# PMOD_OV7670.net
KiCad netlist of a schematic drawn in Altium Designer
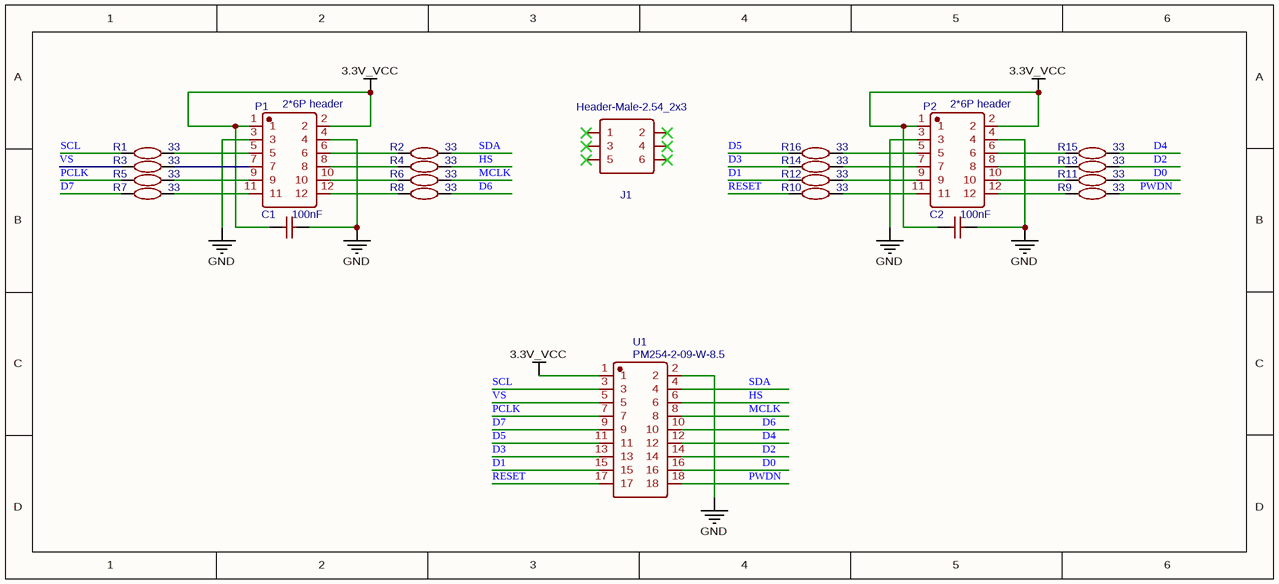
[diagram p0: PMOD_OV7670.schdoc]

(export (version "E")
  (design (tool "Eeschema 10.0.6"))
  (components
    (comp (ref "C1")
      (value "100nF")
      (footprint "C0603")
      (fields
        (field (name "BOM_MANUFACTURER PART") "CL10F104ZB8NNNC")
        (field (name "BOM_SUPPLIER PART") "C1688")
      )
      (libsource (lib "altium-import") (part "root_0_100nF_"))
    )
    (comp (ref "C2")
      (value "100nF")
      (footprint "C0603")
      (fields
        (field (name "BOM_MANUFACTURER PART") "CL10F104ZB8NNNC")
        (field (name "BOM_SUPPLIER PART") "C1688")
      )
      (libsource (lib "altium-import") (part "root_0_100nF_"))
    )
    (comp (ref "J1")
      (value "Header-Male-2.54_2x3")
      (footprint "HDR-TH_6P-P2.54-V-M-R2-C3-S2.54-1")
      (fields (field (name "BOM_SUPPLIER PART") "C65114"))
      (libsource (lib "altium-import") (part "root_0_Header-Male-2.54_2x3_"))
    )
    (comp (ref "P1")
      (value "2*6P header")
      (footprint "HDR-TH_12P-P2.54-H-M-R2-C6-S2.54-W12.5")
      (fields (field (name "BOM_SUPPLIER PART") "C60565"))
      (libsource (lib "altium-import") (part "root_0_2*6P header_"))
    )
    (comp (ref "P2")
      (value "2*6P header")
      (footprint "HDR-TH_12P-P2.54-H-M-R2-C6-S2.54-W12.5")
      (fields (field (name "BOM_SUPPLIER PART") "C60565"))
      (libsource (lib "altium-import") (part "root_0_2*6P header_"))
    )
    (comp (ref "R1")
      (value "33")
      (footprint "R0603")
      (fields
        (field (name "BOM_MANUFACTURER PART") "RTT0333R0FTP")
        (field (name "BOM_SUPPLIER PART") "C103557")
      )
      (libsource (lib "altium-import") (part "root_0_33_"))
    )
    (comp (ref "R2")
      (value "33")
      (footprint "R0603")
      (fields
        (field (name "BOM_MANUFACTURER PART") "RTT0333R0FTP")
        (field (name "BOM_SUPPLIER PART") "C103557")
      )
      (libsource (lib "altium-import") (part "root_0_33_"))
    )
    (comp (ref "R3")
      (value "33")
      (footprint "R0603")
      (fields
        (field (name "BOM_MANUFACTURER PART") "RTT0333R0FTP")
        (field (name "BOM_SUPPLIER PART") "C103557")
      )
      (libsource (lib "altium-import") (part "root_0_33_"))
    )
    (comp (ref "R4")
      (value "33")
      (footprint "R0603")
      (fields
        (field (name "BOM_MANUFACTURER PART") "RTT0333R0FTP")
        (field (name "BOM_SUPPLIER PART") "C103557")
      )
      (libsource (lib "altium-import") (part "root_0_33_"))
    )
    (comp (ref "R5")
      (value "33")
      (footprint "R0603")
      (fields
        (field (name "BOM_MANUFACTURER PART") "RTT0333R0FTP")
        (field (name "BOM_SUPPLIER PART") "C103557")
      )
      (libsource (lib "altium-import") (part "root_0_33_"))
    )
    (comp (ref "R6")
      (value "33")
      (footprint "R0603")
      (fields
        (field (name "BOM_MANUFACTURER PART") "RTT0333R0FTP")
        (field (name "BOM_SUPPLIER PART") "C103557")
      )
      (libsource (lib "altium-import") (part "root_0_33_"))
    )
    (comp (ref "R7")
      (value "33")
      (footprint "R0603")
      (fields
        (field (name "BOM_MANUFACTURER PART") "RTT0333R0FTP")
        (field (name "BOM_SUPPLIER PART") "C103557")
      )
      (libsource (lib "altium-import") (part "root_0_33_"))
    )
    (comp (ref "R8")
      (value "33")
      (footprint "R0603")
      (fields
        (field (name "BOM_MANUFACTURER PART") "RTT0333R0FTP")
        (field (name "BOM_SUPPLIER PART") "C103557")
      )
      (libsource (lib "altium-import") (part "root_0_33_"))
    )
    (comp (ref "R9")
      (value "33")
      (footprint "R0603")
      (fields
        (field (name "BOM_MANUFACTURER PART") "RTT0333R0FTP")
        (field (name "BOM_SUPPLIER PART") "C103557")
      )
      (libsource (lib "altium-import") (part "root_0_33_"))
    )
    (comp (ref "R10")
      (value "33")
      (footprint "R0603")
      (fields
        (field (name "BOM_MANUFACTURER PART") "RTT0333R0FTP")
        (field (name "BOM_SUPPLIER PART") "C103557")
      )
      (libsource (lib "altium-import") (part "root_0_33_"))
    )
    (comp (ref "R11")
      (value "33")
      (footprint "R0603")
      (fields
        (field (name "BOM_MANUFACTURER PART") "RTT0333R0FTP")
        (field (name "BOM_SUPPLIER PART") "C103557")
      )
      (libsource (lib "altium-import") (part "root_0_33_"))
    )
    (comp (ref "R12")
      (value "33")
      (footprint "R0603")
      (fields
        (field (name "BOM_MANUFACTURER PART") "RTT0333R0FTP")
        (field (name "BOM_SUPPLIER PART") "C103557")
      )
      (libsource (lib "altium-import") (part "root_0_33_"))
    )
    (comp (ref "R13")
      (value "33")
      (footprint "R0603")
      (fields
        (field (name "BOM_MANUFACTURER PART") "RTT0333R0FTP")
        (field (name "BOM_SUPPLIER PART") "C103557")
      )
      (libsource (lib "altium-import") (part "root_0_33_"))
    )
    (comp (ref "R14")
      (value "33")
      (footprint "R0603")
      (fields
        (field (name "BOM_MANUFACTURER PART") "RTT0333R0FTP")
        (field (name "BOM_SUPPLIER PART") "C103557")
      )
      (libsource (lib "altium-import") (part "root_0_33_"))
    )
    (comp (ref "R15")
      (value "33")
      (footprint "R0603")
      (fields
        (field (name "BOM_MANUFACTURER PART") "RTT0333R0FTP")
        (field (name "BOM_SUPPLIER PART") "C103557")
      )
      (libsource (lib "altium-import") (part "root_0_33_"))
    )
    (comp (ref "R16")
      (value "33")
      (footprint "R0603")
      (fields
        (field (name "BOM_MANUFACTURER PART") "RTT0333R0FTP")
        (field (name "BOM_SUPPLIER PART") "C103557")
      )
      (libsource (lib "altium-import") (part "root_0_33_"))
    )
    (comp (ref "U1")
      (value "PM254-2-09-W-8.5")
      (footprint "HDR-TH_18P-P2.54-H-F-R2-C9-W8.5")
      (fields (field (name "BOM_SUPPLIER PART") "C2897429") (field (name "CONTRIBUTOR") "LCSC"))
      (libsource (lib "altium-import") (part "root_0_PM254-2-09-W-8.5_"))
    )
  )
  (nets
    (net (code "1") (name "/D0") (class "Default")
      (node (ref "R11") (pin "2") (pinfunction "2_2") (pintype "passive"))
      (node (ref "U1") (pin "16") (pinfunction "16_16") (pintype "passive"))
    )
    (net (code "2") (name "/D1") (class "Default")
      (node (ref "R12") (pin "1") (pinfunction "1_1") (pintype "passive"))
      (node (ref "U1") (pin "15") (pinfunction "15_15") (pintype "passive"))
    )
    (net (code "3") (name "/D2") (class "Default")
      (node (ref "R13") (pin "2") (pinfunction "2_2") (pintype "passive"))
      (node (ref "U1") (pin "14") (pinfunction "14_14") (pintype "passive"))
    )
    (net (code "4") (name "/D3") (class "Default")
      (node (ref "R14") (pin "1") (pinfunction "1_1") (pintype "passive"))
      (node (ref "U1") (pin "13") (pinfunction "13_13") (pintype "passive"))
    )
    (net (code "5") (name "/D4") (class "Default")
      (node (ref "R15") (pin "2") (pinfunction "2_2") (pintype "passive"))
      (node (ref "U1") (pin "12") (pinfunction "12_12") (pintype "passive"))
    )
    (net (code "6") (name "/D5") (class "Default")
      (node (ref "R16") (pin "1") (pinfunction "1_1") (pintype "passive"))
      (node (ref "U1") (pin "11") (pinfunction "11_11") (pintype "passive"))
    )
    (net (code "7") (name "/D6") (class "Default")
      (node (ref "R8") (pin "2") (pinfunction "2_2") (pintype "passive"))
      (node (ref "U1") (pin "10") (pinfunction "10_10") (pintype "passive"))
    )
    (net (code "8") (name "/D7") (class "Default")
      (node (ref "R7") (pin "1") (pinfunction "1_1") (pintype "passive"))
      (node (ref "U1") (pin "9") (pinfunction "9_9") (pintype "passive"))
    )
    (net (code "9") (name "/HS") (class "Default")
      (node (ref "R4") (pin "2") (pinfunction "2_2") (pintype "passive"))
      (node (ref "U1") (pin "6") (pinfunction "6_6") (pintype "passive"))
    )
    (net (code "10") (name "/MCLK") (class "Default")
      (node (ref "R6") (pin "2") (pinfunction "2_2") (pintype "passive"))
      (node (ref "U1") (pin "8") (pinfunction "8_8") (pintype "passive"))
    )
    (net (code "11") (name "/PCLK") (class "Default")
      (node (ref "R5") (pin "1") (pinfunction "1_1") (pintype "passive"))
      (node (ref "U1") (pin "7") (pinfunction "7_7") (pintype "passive"))
    )
    (net (code "12") (name "/PWDN") (class "Default")
      (node (ref "R9") (pin "2") (pinfunction "2_2") (pintype "passive"))
      (node (ref "U1") (pin "18") (pinfunction "18_18") (pintype "passive"))
    )
    (net (code "13") (name "/RESET") (class "Default")
      (node (ref "R10") (pin "1") (pinfunction "1_1") (pintype "passive"))
      (node (ref "U1") (pin "17") (pinfunction "17_17") (pintype "passive"))
    )
    (net (code "14") (name "/SCL") (class "Default")
      (node (ref "R1") (pin "1") (pinfunction "1_1") (pintype "passive"))
      (node (ref "U1") (pin "3") (pinfunction "3_3") (pintype "passive"))
    )
    (net (code "15") (name "/SDA") (class "Default")
      (node (ref "R2") (pin "2") (pinfunction "2_2") (pintype "passive"))
      (node (ref "U1") (pin "4") (pinfunction "4_4") (pintype "passive"))
    )
    (net (code "16") (name "/VS") (class "Default")
      (node (ref "R3") (pin "1") (pinfunction "1_1") (pintype "passive"))
      (node (ref "U1") (pin "5") (pinfunction "5_5") (pintype "passive"))
    )
    (net (code "17") (name "3.3V_VCC") (class "Default")
      (node (ref "C1") (pin "1") (pinfunction "1_1") (pintype "passive"))
      (node (ref "C2") (pin "1") (pinfunction "1_1") (pintype "passive"))
      (node (ref "P1") (pin "1") (pinfunction "1_1") (pintype "passive"))
      (node (ref "P1") (pin "2") (pinfunction "2_2") (pintype "passive"))
      (node (ref "P2") (pin "1") (pinfunction "1_1") (pintype "passive"))
      (node (ref "P2") (pin "2") (pinfunction "2_2") (pintype "passive"))
      (node (ref "U1") (pin "1") (pinfunction "1_1") (pintype "passive"))
    )
    (net (code "18") (name "GND") (class "Default")
      (node (ref "C1") (pin "2") (pinfunction "2_2") (pintype "passive"))
      (node (ref "C2") (pin "2") (pinfunction "2_2") (pintype "passive"))
      (node (ref "P1") (pin "3") (pinfunction "3_3") (pintype "passive"))
      (node (ref "P1") (pin "4") (pinfunction "4_4") (pintype "passive"))
      (node (ref "P2") (pin "3") (pinfunction "3_3") (pintype "passive"))
      (node (ref "P2") (pin "4") (pinfunction "4_4") (pintype "passive"))
      (node (ref "U1") (pin "2") (pinfunction "2_2") (pintype "passive"))
    )
    (net (code "19") (name "Net-(P1-Pad5)") (class "Default")
      (node (ref "P1") (pin "5") (pinfunction "5_5") (pintype "passive"))
      (node (ref "R1") (pin "2") (pinfunction "2_2") (pintype "passive"))
    )
    (net (code "20") (name "Net-(P1-Pad6)") (class "Default")
      (node (ref "P1") (pin "6") (pinfunction "6_6") (pintype "passive"))
      (node (ref "R2") (pin "1") (pinfunction "1_1") (pintype "passive"))
    )
    (net (code "21") (name "Net-(P1-Pad7)") (class "Default")
      (node (ref "P1") (pin "7") (pinfunction "7_7") (pintype "passive"))
      (node (ref "R3") (pin "2") (pinfunction "2_2") (pintype "passive"))
    )
    (net (code "22") (name "Net-(P1-Pad8)") (class "Default")
      (node (ref "P1") (pin "8") (pinfunction "8_8") (pintype "passive"))
      (node (ref "R4") (pin "1") (pinfunction "1_1") (pintype "passive"))
    )
    (net (code "23") (name "Net-(P1-Pad9)") (class "Default")
      (node (ref "P1") (pin "9") (pinfunction "9_9") (pintype "passive"))
      (node (ref "R5") (pin "2") (pinfunction "2_2") (pintype "passive"))
    )
    (net (code "24") (name "Net-(P1-Pad10)") (class "Default")
      (node (ref "P1") (pin "10") (pinfunction "10_10") (pintype "passive"))
      (node (ref "R6") (pin "1") (pinfunction "1_1") (pintype "passive"))
    )
    (net (code "25") (name "Net-(P1-Pad11)") (class "Default")
      (node (ref "P1") (pin "11") (pinfunction "11_11") (pintype "passive"))
      (node (ref "R7") (pin "2") (pinfunction "2_2") (pintype "passive"))
    )
    (net (code "26") (name "Net-(P1-Pad12)") (class "Default")
      (node (ref "P1") (pin "12") (pinfunction "12_12") (pintype "passive"))
      (node (ref "R8") (pin "1") (pinfunction "1_1") (pintype "passive"))
    )
    (net (code "27") (name "Net-(P2-Pad5)") (class "Default")
      (node (ref "P2") (pin "5") (pinfunction "5_5") (pintype "passive"))
      (node (ref "R16") (pin "2") (pinfunction "2_2") (pintype "passive"))
    )
    (net (code "28") (name "Net-(P2-Pad6)") (class "Default")
      (node (ref "P2") (pin "6") (pinfunction "6_6") (pintype "passive"))
      (node (ref "R15") (pin "1") (pinfunction "1_1") (pintype "passive"))
    )
    (net (code "29") (name "Net-(P2-Pad7)") (class "Default")
      (node (ref "P2") (pin "7") (pinfunction "7_7") (pintype "passive"))
      (node (ref "R14") (pin "2") (pinfunction "2_2") (pintype "passive"))
    )
    (net (code "30") (name "Net-(P2-Pad8)") (class "Default")
      (node (ref "P2") (pin "8") (pinfunction "8_8") (pintype "passive"))
      (node (ref "R13") (pin "1") (pinfunction "1_1") (pintype "passive"))
    )
    (net (code "31") (name "Net-(P2-Pad9)") (class "Default")
      (node (ref "P2") (pin "9") (pinfunction "9_9") (pintype "passive"))
      (node (ref "R12") (pin "2") (pinfunction "2_2") (pintype "passive"))
    )
    (net (code "32") (name "Net-(P2-Pad10)") (class "Default")
      (node (ref "P2") (pin "10") (pinfunction "10_10") (pintype "passive"))
      (node (ref "R11") (pin "1") (pinfunction "1_1") (pintype "passive"))
    )
    (net (code "33") (name "Net-(P2-Pad11)") (class "Default")
      (node (ref "P2") (pin "11") (pinfunction "11_11") (pintype "passive"))
      (node (ref "R10") (pin "2") (pinfunction "2_2") (pintype "passive"))
    )
    (net (code "34") (name "Net-(P2-Pad12)") (class "Default")
      (node (ref "P2") (pin "12") (pinfunction "12_12") (pintype "passive"))
      (node (ref "R9") (pin "1") (pinfunction "1_1") (pintype "passive"))
    )
    (net (code "35") (name "unconnected-(J1-Pad1)") (class "Default")
      (node (ref "J1") (pin "1") (pinfunction "1_1") (pintype "passive+no_connect"))
    )
    (net (code "36") (name "unconnected-(J1-Pad2)") (class "Default")
      (node (ref "J1") (pin "2") (pinfunction "2_2") (pintype "passive+no_connect"))
    )
    (net (code "37") (name "unconnected-(J1-Pad3)") (class "Default")
      (node (ref "J1") (pin "3") (pinfunction "3_3") (pintype "passive+no_connect"))
    )
    (net (code "38") (name "unconnected-(J1-Pad4)") (class "Default")
      (node (ref "J1") (pin "4") (pinfunction "4_4") (pintype "passive+no_connect"))
    )
    (net (code "39") (name "unconnected-(J1-Pad5)") (class "Default")
      (node (ref "J1") (pin "5") (pinfunction "5_5") (pintype "passive+no_connect"))
    )
    (net (code "40") (name "unconnected-(J1-Pad6)") (class "Default")
      (node (ref "J1") (pin "6") (pinfunction "6_6") (pintype "passive+no_connect"))
    )
  )
)
